# 3_Unextended55_mcu.net
KiCad netlist of a schematic drawn in Altium Designer
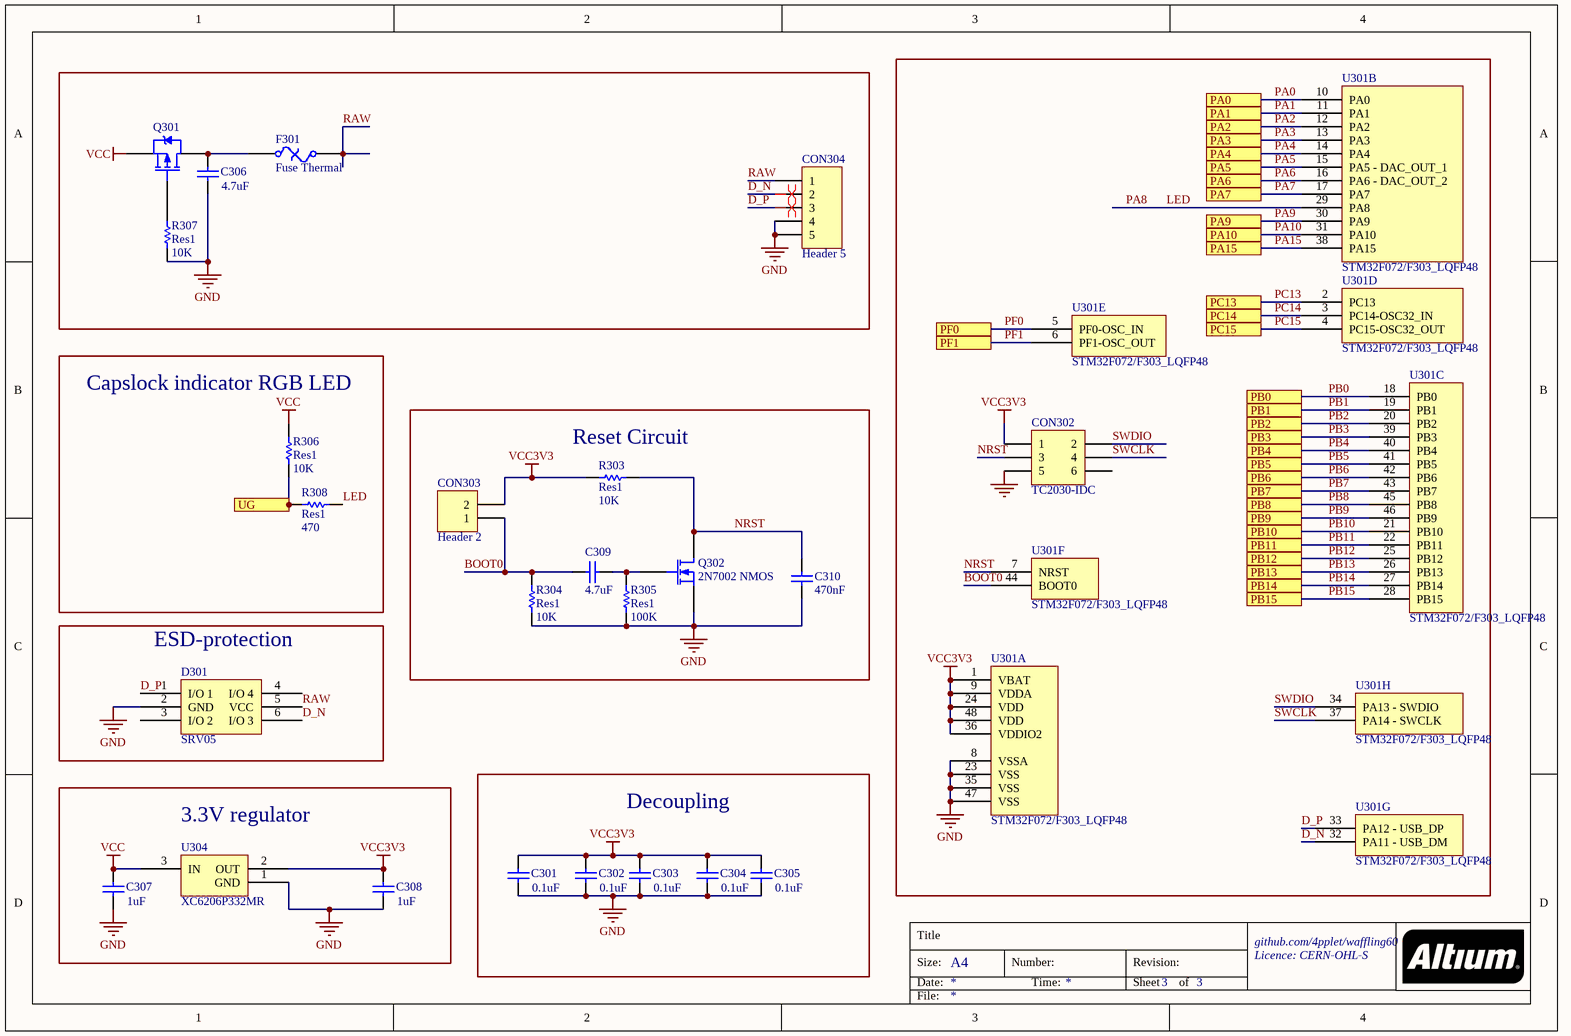
[diagram p0: 3_Unextended55_mcu.SchDoc]

(export (version "E")
  (design (tool "Eeschema 10.0.6"))
  (components
    (comp (ref "C301")
      (value "0.1uF")
      (footprint "C0603[1608]")
      (description "Capacitor")
      (fields (field (name "LCSC PART #") "C14663") (field (name "MRF.PART") "CC0603KRX7R9BB104"))
      (libsource (lib "Miscellaneous Devices") (part "Cap"))
    )
    (comp (ref "C302")
      (value "0.1uF")
      (footprint "C0603[1608]")
      (description "Capacitor")
      (fields (field (name "LCSC PART #") "C14663") (field (name "MRF.PART") "CC0603KRX7R9BB104"))
      (libsource (lib "Miscellaneous Devices") (part "Cap"))
    )
    (comp (ref "C303")
      (value "0.1uF")
      (footprint "C0603[1608]")
      (description "Capacitor")
      (fields (field (name "LCSC PART #") "C14663") (field (name "MRF.PART") "CC0603KRX7R9BB104"))
      (libsource (lib "Miscellaneous Devices") (part "Cap"))
    )
    (comp (ref "C304")
      (value "0.1uF")
      (footprint "C0603[1608]")
      (description "Capacitor")
      (fields (field (name "LCSC PART #") "C14663") (field (name "MRF.PART") "CC0603KRX7R9BB104"))
      (libsource (lib "Miscellaneous Devices") (part "Cap"))
    )
    (comp (ref "C305")
      (value "0.1uF")
      (footprint "C0603[1608]")
      (description "Capacitor")
      (fields (field (name "LCSC PART #") "C14663") (field (name "MRF.PART") "CC0603KRX7R9BB104"))
      (libsource (lib "Miscellaneous Devices") (part "Cap"))
    )
    (comp (ref "C306")
      (value "4.7uF")
      (footprint "C0603[1608]")
      (description "Capacitor")
      (fields (field (name "LCSC PART #") "C19666") (field (name "MRF.PART") "CL10A475KO8NNNC"))
      (libsource (lib "Miscellaneous Devices") (part "Cap"))
    )
    (comp (ref "C307")
      (value "1uF")
      (footprint "C0603[1608]")
      (description "Capacitor")
      (fields (field (name "LCSC PART #") "C15849") (field (name "MRF.PART") "CL10A105KB8NNNC"))
      (libsource (lib "Miscellaneous Devices") (part "Cap"))
    )
    (comp (ref "C308")
      (value "1uF")
      (footprint "C0603[1608]")
      (description "Capacitor")
      (fields (field (name "LCSC PART #") "C15849") (field (name "MRF.PART") "CL10A105KB8NNNC"))
      (libsource (lib "Miscellaneous Devices") (part "Cap"))
    )
    (comp (ref "C309")
      (value "4.7uF")
      (footprint "C0603[1608]")
      (description "Capacitor")
      (fields (field (name "LCSC PART #") "C19666") (field (name "MRF.PART") "CL10A475KO8NNNC"))
      (libsource (lib "Miscellaneous Devices") (part "Cap"))
    )
    (comp (ref "C310")
      (value "470nF")
      (footprint "C0603[1608]")
      (description "Capacitor")
      (fields (field (name "LCSC PART #") "C1623") (field (name "MRF.PART") "CL10B474KA8NNNC"))
      (libsource (lib "Miscellaneous Devices") (part "Cap"))
    )
    (comp (ref "CON302")
      (value "TC2030-IDC")
      (footprint "TC2030-IDC-NL")
      (description "Header, 3-Pin, Dual row")
      (libsource (lib "Miscellaneous Connectors") (part "Header 3X2"))
    )
    (comp (ref "CON303")
      (value "Header 2")
      (footprint "HDR1X2")
      (description "Header, 2-Pin")
      (libsource (lib "Miscellaneous Connectors") (part "Header 2"))
    )
    (comp (ref "CON304")
      (value "Header 5")
      (footprint "JST SM04B-SRSS-TB")
      (description "JST for USB daughter board")
      (fields (field (name "LCSC PART #") "C160404") (field (name "MRF.PART") "SM04B-SRSS-TB(LF)(SN)"))
      (libsource (lib "Miscellaneous Connectors") (part "Header 5"))
    )
    (comp (ref "D301")
      (value "SRV05")
      (footprint "SOT-23-6")
      (fields (field (name "LCSC PART #") "C85364") (field (name "MRF.PART") "SRV05-4-P-T7"))
      (libsource (lib "Keebs") (part "SRV05"))
    )
    (comp (ref "F301")
      (value "Fuse Thermal")
      (footprint "C1206[3216]")
      (description "Thermal Fuse")
      (fields (field (name "LCSC PART #") "C135338") (field (name "MRF.PART") "ASMD1206-050"))
      (libsource (lib "Miscellaneous Devices") (part "Fuse Thermal"))
    )
    (comp (ref "Q301")
      (value "PMOS-2")
      (footprint "SOT-23-3")
      (description "P-Channel Power MOSFET")
      (fields (field (name "LCSC PART #") "C10487") (field (name "MRF.PART") "SI2301CDS-T1-GE3"))
      (libsource (lib "Miscellaneous Devices") (part "PMOS-2"))
    )
    (comp (ref "Q302")
      (value "2N7002 NMOS")
      (footprint "SOT-23-3")
      (description "N-Channel MOSFET")
      (fields (field (name "LCSC PART #") "C8545") (field (name "MRF.PART") "2N7002"))
      (libsource (lib "Miscellaneous Devices") (part "MOSFET-N"))
    )
    (comp (ref "R303")
      (value "Res1")
      (footprint "R0603[1608]")
      (description "Resistor")
      (fields
        (field (name "ALTIUM_VALUE") "10K")
        (field (name "LCSC PART #") "C25804")
        (field (name "MRF.PART") "0603WAF1002T5E")
      )
      (libsource (lib "Miscellaneous Devices") (part "Res1"))
    )
    (comp (ref "R304")
      (value "Res1")
      (footprint "R0603[1608]")
      (description "Resistor")
      (fields
        (field (name "ALTIUM_VALUE") "10K")
        (field (name "LCSC PART #") "C25804")
        (field (name "MRF.PART") "0603WAF1002T5E")
      )
      (libsource (lib "Miscellaneous Devices") (part "Res1"))
    )
    (comp (ref "R305")
      (value "Res1")
      (footprint "R0603[1608]")
      (description "Resistor")
      (fields
        (field (name "ALTIUM_VALUE") "100K")
        (field (name "LCSC PART #") "C25803")
        (field (name "MRF.PART") "0603WAF1003T5E")
      )
      (libsource (lib "Miscellaneous Devices") (part "Res1"))
    )
    (comp (ref "R306")
      (value "Res1")
      (footprint "R0603[1608]")
      (description "Resistor")
      (fields
        (field (name "ALTIUM_VALUE") "10K")
        (field (name "LCSC PART #") "C25804")
        (field (name "MRF.PART") "0603WAF1002T5E")
      )
      (libsource (lib "Miscellaneous Devices") (part "Res1"))
    )
    (comp (ref "R307")
      (value "Res1")
      (footprint "R0603[1608]")
      (description "Resistor")
      (fields
        (field (name "ALTIUM_VALUE") "10K")
        (field (name "LCSC PART #") "C25804")
        (field (name "MRF.PART") "0603WAF1002T5E")
      )
      (libsource (lib "Miscellaneous Devices") (part "Res1"))
    )
    (comp (ref "R308")
      (value "Res1")
      (footprint "R0603[1608]")
      (description "Resistor")
      (fields
        (field (name "ALTIUM_VALUE") "470")
        (field (name "LCSC PART #") "C23179")
        (field (name "MRF.PART") "0603WAF4700T5E")
      )
      (libsource (lib "Miscellaneous Devices") (part "Res1"))
    )
    (comp (ref "U301")
      (value "STM32F072/F303_LQFP48")
      (footprint "STM32 - LQFP48, 7x7mm")
      (fields (field (name "LCSC PART #") "C915660") (field (name "MRF.PART") "APM32F072CBT6"))
      (libsource (lib "Keebs") (part "STM32F072/F303_LQFP48"))
    )
    (comp (ref "U304")
      (value "XC6206P332MR")
      (footprint "SOT-23-3")
      (fields (field (name "LCSC PART #") "C5446"))
      (libsource (lib "Keebs") (part "SOT23 LDO"))
    )
  )
  (nets
    (net (code "1") (name "/BOOT0") (class "Default")
      (node (ref "C309") (pin "1") (pinfunction "1_1") (pintype "passive"))
      (node (ref "CON303") (pin "1") (pinfunction "1_1") (pintype "passive"))
      (node (ref "R304") (pin "1") (pinfunction "1_1") (pintype "passive"))
      (node (ref "U301") (pin "44") (pinfunction "BOOT0_44") (pintype "passive"))
    )
    (net (code "2") (name "/D_N") (class "Default")
      (node (ref "CON304") (pin "2") (pinfunction "2_2") (pintype "passive"))
      (node (ref "D301") (pin "6") (pinfunction "I/O_3_6") (pintype "passive"))
      (node (ref "U301") (pin "32") (pinfunction "PA11_-_USB_DM_32") (pintype "passive"))
    )
    (net (code "3") (name "/D_P") (class "Default")
      (node (ref "CON304") (pin "3") (pinfunction "3_3") (pintype "passive"))
      (node (ref "D301") (pin "1") (pinfunction "I/O_1_1") (pintype "passive"))
      (node (ref "U301") (pin "33") (pinfunction "PA12_-_USB_DP_33") (pintype "passive"))
    )
    (net (code "4") (name "/LED") (class "Default")
      (node (ref "R308") (pin "2") (pinfunction "2_2") (pintype "passive"))
      (node (ref "U301") (pin "29") (pinfunction "PA8_29") (pintype "passive"))
    )
    (net (code "5") (name "/NRST") (class "Default")
      (node (ref "C310") (pin "1") (pinfunction "1_1") (pintype "passive"))
      (node (ref "CON302") (pin "3") (pinfunction "3_3") (pintype "passive"))
      (node (ref "Q302") (pin "3") (pinfunction "D_3") (pintype "passive"))
      (node (ref "R303") (pin "2") (pinfunction "2_2") (pintype "passive"))
      (node (ref "U301") (pin "7") (pinfunction "NRST_7") (pintype "passive"))
    )
    (net (code "6") (name "/PA0") (class "Default")
      (node (ref "U301") (pin "10") (pinfunction "PA0_10") (pintype "passive"))
    )
    (net (code "7") (name "/PA1") (class "Default")
      (node (ref "U301") (pin "11") (pinfunction "PA1_11") (pintype "passive"))
    )
    (net (code "8") (name "/PA2") (class "Default")
      (node (ref "U301") (pin "12") (pinfunction "PA2_12") (pintype "passive"))
    )
    (net (code "9") (name "/PA3") (class "Default")
      (node (ref "U301") (pin "13") (pinfunction "PA3_13") (pintype "passive"))
    )
    (net (code "10") (name "/PA4") (class "Default")
      (node (ref "U301") (pin "14") (pinfunction "PA4_14") (pintype "passive"))
    )
    (net (code "11") (name "/PA5") (class "Default")
      (node (ref "U301") (pin "15") (pinfunction "PA5_-_DAC_OUT_1_15") (pintype "passive"))
    )
    (net (code "12") (name "/PA6") (class "Default")
      (node (ref "U301") (pin "16") (pinfunction "PA6_-_DAC_OUT_2_16") (pintype "passive"))
    )
    (net (code "13") (name "/PA7") (class "Default")
      (node (ref "U301") (pin "17") (pinfunction "PA7_17") (pintype "passive"))
    )
    (net (code "14") (name "/PA9") (class "Default")
      (node (ref "U301") (pin "30") (pinfunction "PA9_30") (pintype "passive"))
    )
    (net (code "15") (name "/PA10") (class "Default")
      (node (ref "U301") (pin "31") (pinfunction "PA10_31") (pintype "passive"))
    )
    (net (code "16") (name "/PA15") (class "Default")
      (node (ref "U301") (pin "38") (pinfunction "PA15_38") (pintype "passive"))
    )
    (net (code "17") (name "/PB0") (class "Default")
      (node (ref "U301") (pin "18") (pinfunction "PB0_18") (pintype "passive"))
    )
    (net (code "18") (name "/PB1") (class "Default")
      (node (ref "U301") (pin "19") (pinfunction "PB1_19") (pintype "passive"))
    )
    (net (code "19") (name "/PB2") (class "Default")
      (node (ref "U301") (pin "20") (pinfunction "PB2_20") (pintype "passive"))
    )
    (net (code "20") (name "/PB3") (class "Default")
      (node (ref "U301") (pin "39") (pinfunction "PB3_39") (pintype "passive"))
    )
    (net (code "21") (name "/PB4") (class "Default")
      (node (ref "U301") (pin "40") (pinfunction "PB4_40") (pintype "passive"))
    )
    (net (code "22") (name "/PB5") (class "Default")
      (node (ref "U301") (pin "41") (pinfunction "PB5_41") (pintype "passive"))
    )
    (net (code "23") (name "/PB6") (class "Default")
      (node (ref "U301") (pin "42") (pinfunction "PB6_42") (pintype "passive"))
    )
    (net (code "24") (name "/PB7") (class "Default")
      (node (ref "U301") (pin "43") (pinfunction "PB7_43") (pintype "passive"))
    )
    (net (code "25") (name "/PB8") (class "Default")
      (node (ref "U301") (pin "45") (pinfunction "PB8_45") (pintype "passive"))
    )
    (net (code "26") (name "/PB9") (class "Default")
      (node (ref "U301") (pin "46") (pinfunction "PB9_46") (pintype "passive"))
    )
    (net (code "27") (name "/PB10") (class "Default")
      (node (ref "U301") (pin "21") (pinfunction "PB10_21") (pintype "passive"))
    )
    (net (code "28") (name "/PB11") (class "Default")
      (node (ref "U301") (pin "22") (pinfunction "PB11_22") (pintype "passive"))
    )
    (net (code "29") (name "/PB12") (class "Default")
      (node (ref "U301") (pin "25") (pinfunction "PB12_25") (pintype "passive"))
    )
    (net (code "30") (name "/PB13") (class "Default")
      (node (ref "U301") (pin "26") (pinfunction "PB13_26") (pintype "passive"))
    )
    (net (code "31") (name "/PB14") (class "Default")
      (node (ref "U301") (pin "27") (pinfunction "PB14_27") (pintype "passive"))
    )
    (net (code "32") (name "/PB15") (class "Default")
      (node (ref "U301") (pin "28") (pinfunction "PB15_28") (pintype "passive"))
    )
    (net (code "33") (name "/PC13") (class "Default")
      (node (ref "U301") (pin "2") (pinfunction "PC13_2") (pintype "passive"))
    )
    (net (code "34") (name "/PC14") (class "Default")
      (node (ref "U301") (pin "3") (pinfunction "PC14-OSC32_IN_3") (pintype "passive"))
    )
    (net (code "35") (name "/PC15") (class "Default")
      (node (ref "U301") (pin "4") (pinfunction "PC15-OSC32_OUT_4") (pintype "passive"))
    )
    (net (code "36") (name "/PF0") (class "Default")
      (node (ref "U301") (pin "5") (pinfunction "PF0-OSC_IN_5") (pintype "passive"))
    )
    (net (code "37") (name "/PF1") (class "Default")
      (node (ref "U301") (pin "6") (pinfunction "PF1-OSC_OUT_6") (pintype "passive"))
    )
    (net (code "38") (name "/RAW") (class "Default")
      (node (ref "CON304") (pin "1") (pinfunction "1_1") (pintype "passive"))
      (node (ref "D301") (pin "5") (pinfunction "VCC_5") (pintype "passive"))
      (node (ref "F301") (pin "2") (pinfunction "2_2") (pintype "passive"))
    )
    (net (code "39") (name "/SWCLK") (class "Default")
      (node (ref "CON302") (pin "4") (pinfunction "4_4") (pintype "passive"))
      (node (ref "U301") (pin "37") (pinfunction "PA14_-_SWCLK_37") (pintype "passive"))
    )
    (net (code "40") (name "/SWDIO") (class "Default")
      (node (ref "CON302") (pin "2") (pinfunction "2_2") (pintype "passive"))
      (node (ref "U301") (pin "34") (pinfunction "PA13_-_SWDIO_34") (pintype "passive"))
    )
    (net (code "41") (name "/UG") (class "Default")
      (node (ref "R306") (pin "2") (pinfunction "2_2") (pintype "passive"))
      (node (ref "R308") (pin "1") (pinfunction "1_1") (pintype "passive"))
    )
    (net (code "42") (name "GND") (class "Default")
      (node (ref "C301") (pin "1") (pinfunction "1_1") (pintype "passive"))
      (node (ref "C302") (pin "1") (pinfunction "1_1") (pintype "passive"))
      (node (ref "C303") (pin "1") (pinfunction "1_1") (pintype "passive"))
      (node (ref "C304") (pin "1") (pinfunction "1_1") (pintype "passive"))
      (node (ref "C305") (pin "1") (pinfunction "1_1") (pintype "passive"))
      (node (ref "C306") (pin "1") (pinfunction "1_1") (pintype "passive"))
      (node (ref "C307") (pin "1") (pinfunction "1_1") (pintype "passive"))
      (node (ref "C308") (pin "1") (pinfunction "1_1") (pintype "passive"))
      (node (ref "C310") (pin "2") (pinfunction "2_2") (pintype "passive"))
      (node (ref "CON302") (pin "5") (pinfunction "5_5") (pintype "passive"))
      (node (ref "CON304") (pin "4") (pinfunction "4_4") (pintype "passive"))
      (node (ref "CON304") (pin "5") (pinfunction "5_5") (pintype "passive"))
      (node (ref "D301") (pin "2") (pinfunction "GND_2") (pintype "passive"))
      (node (ref "Q302") (pin "2") (pinfunction "S_2") (pintype "passive"))
      (node (ref "R304") (pin "2") (pinfunction "2_2") (pintype "passive"))
      (node (ref "R305") (pin "2") (pinfunction "2_2") (pintype "passive"))
      (node (ref "R307") (pin "2") (pinfunction "2_2") (pintype "passive"))
      (node (ref "U301") (pin "23") (pinfunction "VSS_23") (pintype "passive"))
      (node (ref "U301") (pin "35") (pinfunction "VSS_35") (pintype "passive"))
      (node (ref "U301") (pin "47") (pinfunction "VSS_47") (pintype "passive"))
      (node (ref "U301") (pin "8") (pinfunction "VSSA_8") (pintype "passive"))
      (node (ref "U304") (pin "1") (pinfunction "GND_1") (pintype "passive"))
    )
    (net (code "43") (name "Net-(Q301-D)") (class "Default")
      (node (ref "C306") (pin "2") (pinfunction "2_2") (pintype "passive"))
      (node (ref "F301") (pin "1") (pinfunction "1_1") (pintype "passive"))
      (node (ref "Q301") (pin "3") (pinfunction "D_3") (pintype "passive"))
    )
    (net (code "44") (name "Net-(Q301-G)") (class "Default")
      (node (ref "Q301") (pin "1") (pinfunction "G_1") (pintype "passive"))
      (node (ref "R307") (pin "1") (pinfunction "1_1") (pintype "passive"))
    )
    (net (code "45") (name "Net-(Q302-G)") (class "Default")
      (node (ref "C309") (pin "2") (pinfunction "2_2") (pintype "passive"))
      (node (ref "Q302") (pin "1") (pinfunction "G_1") (pintype "passive"))
      (node (ref "R305") (pin "1") (pinfunction "1_1") (pintype "passive"))
    )
    (net (code "46") (name "VCC") (class "Default")
      (node (ref "C307") (pin "2") (pinfunction "2_2") (pintype "passive"))
      (node (ref "Q301") (pin "2") (pinfunction "S_2") (pintype "passive"))
      (node (ref "R306") (pin "1") (pinfunction "1_1") (pintype "passive"))
      (node (ref "U304") (pin "3") (pinfunction "IN_3") (pintype "passive"))
    )
    (net (code "47") (name "VCC3V3") (class "Default")
      (node (ref "C301") (pin "2") (pinfunction "2_2") (pintype "passive"))
      (node (ref "C302") (pin "2") (pinfunction "2_2") (pintype "passive"))
      (node (ref "C303") (pin "2") (pinfunction "2_2") (pintype "passive"))
      (node (ref "C304") (pin "2") (pinfunction "2_2") (pintype "passive"))
      (node (ref "C305") (pin "2") (pinfunction "2_2") (pintype "passive"))
      (node (ref "C308") (pin "2") (pinfunction "2_2") (pintype "passive"))
      (node (ref "CON302") (pin "1") (pinfunction "1_1") (pintype "passive"))
      (node (ref "CON303") (pin "2") (pinfunction "2_2") (pintype "passive"))
      (node (ref "R303") (pin "1") (pinfunction "1_1") (pintype "passive"))
      (node (ref "U301") (pin "1") (pinfunction "VBAT_1") (pintype "passive"))
      (node (ref "U301") (pin "24") (pinfunction "VDD_24") (pintype "passive"))
      (node (ref "U301") (pin "36") (pinfunction "VDDIO2_36") (pintype "passive"))
      (node (ref "U301") (pin "48") (pinfunction "VDD_48") (pintype "passive"))
      (node (ref "U301") (pin "9") (pinfunction "VDDA_9") (pintype "passive"))
      (node (ref "U304") (pin "2") (pinfunction "OUT_2") (pintype "passive"))
    )
    (net (code "48") (name "unconnected-(CON302-Pad6)") (class "Default")
      (node (ref "CON302") (pin "6") (pinfunction "6_6") (pintype "passive"))
    )
    (net (code "49") (name "unconnected-(D301-I{slash}O_2-Pad3)") (class "Default")
      (node (ref "D301") (pin "3") (pinfunction "I/O_2_3") (pintype "passive"))
    )
    (net (code "50") (name "unconnected-(D301-I{slash}O_4-Pad4)") (class "Default")
      (node (ref "D301") (pin "4") (pinfunction "I/O_4_4") (pintype "passive"))
    )
  )
)
